# NIXIE_2.net
KiCad netlist of a schematic drawn in Altium Designer
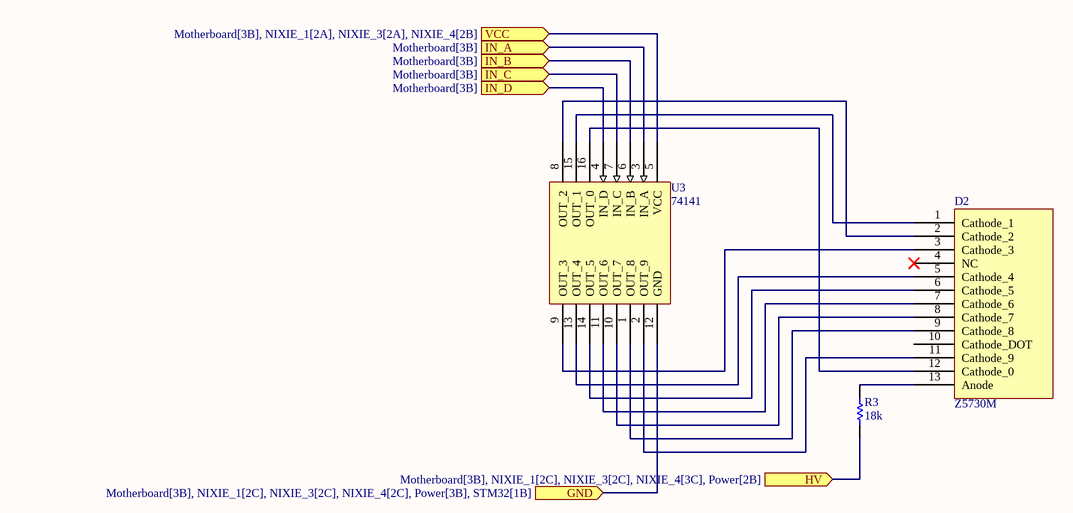
[diagram p0: NIXIE_2.SchDoc]

(export (version "E")
  (design (tool "Eeschema 10.0.6"))
  (components
    (comp (ref "D2") (value "Z5730M") (footprint "Z5730M") (libsource (lib "Z5730M") (part "Z5730M")))
    (comp (ref "R3")
      (value "18k")
      (footprint "RESC2013X60X40LL20T25")
      (fields (field (name "MANUFACTURER") "Panasonic") (field (name "PART NUMBER") "ERA6AEB183V"))
      (libsource (lib "Altium Content Vault") (part "RES"))
    )
    (comp (ref "U3") (value "74141") (footprint "DIP-16") (libsource (lib "Z5730M") (part "74141")))
  )
  (nets
    (net (code "1") (name "/GND") (class "Default")
      (node (ref "U3") (pin "12") (pinfunction "GND_12") (pintype "power_in"))
    )
    (net (code "2") (name "/HV") (class "Default")
      (node (ref "R3") (pin "1") (pinfunction "1_1") (pintype "passive"))
    )
    (net (code "3") (name "/IN_A") (class "Default")
      (node (ref "U3") (pin "3") (pinfunction "IN_A_3") (pintype "input"))
    )
    (net (code "4") (name "/IN_B") (class "Default")
      (node (ref "U3") (pin "6") (pinfunction "IN_B_6") (pintype "input"))
    )
    (net (code "5") (name "/IN_C") (class "Default")
      (node (ref "U3") (pin "7") (pinfunction "IN_C_7") (pintype "input"))
    )
    (net (code "6") (name "/IN_D") (class "Default")
      (node (ref "U3") (pin "4") (pinfunction "IN_D_4") (pintype "input"))
    )
    (net (code "7") (name "/VCC") (class "Default")
      (node (ref "U3") (pin "5") (pinfunction "VCC_5") (pintype "power_in"))
    )
    (net (code "8") (name "Net-(D2-Anode)") (class "Default")
      (node (ref "D2") (pin "13") (pinfunction "Anode_13") (pintype "passive"))
      (node (ref "R3") (pin "2") (pinfunction "2_2") (pintype "passive"))
    )
    (net (code "9") (name "Net-(D2-Cathode_0)") (class "Default")
      (node (ref "D2") (pin "12") (pinfunction "Cathode_0_12") (pintype "passive"))
      (node (ref "U3") (pin "16") (pinfunction "OUT_0_16") (pintype "open_collector"))
    )
    (net (code "10") (name "Net-(D2-Cathode_1)") (class "Default")
      (node (ref "D2") (pin "1") (pinfunction "Cathode_1_1") (pintype "passive"))
      (node (ref "U3") (pin "15") (pinfunction "OUT_1_15") (pintype "open_collector"))
    )
    (net (code "11") (name "Net-(D2-Cathode_2)") (class "Default")
      (node (ref "D2") (pin "2") (pinfunction "Cathode_2_2") (pintype "passive"))
      (node (ref "U3") (pin "8") (pinfunction "OUT_2_8") (pintype "open_collector"))
    )
    (net (code "12") (name "Net-(D2-Cathode_3)") (class "Default")
      (node (ref "D2") (pin "3") (pinfunction "Cathode_3_3") (pintype "passive"))
      (node (ref "U3") (pin "9") (pinfunction "OUT_3_9") (pintype "open_collector"))
    )
    (net (code "13") (name "Net-(D2-Cathode_4)") (class "Default")
      (node (ref "D2") (pin "5") (pinfunction "Cathode_4_5") (pintype "passive"))
      (node (ref "U3") (pin "13") (pinfunction "OUT_4_13") (pintype "open_collector"))
    )
    (net (code "14") (name "Net-(D2-Cathode_5)") (class "Default")
      (node (ref "D2") (pin "6") (pinfunction "Cathode_5_6") (pintype "passive"))
      (node (ref "U3") (pin "14") (pinfunction "OUT_5_14") (pintype "open_collector"))
    )
    (net (code "15") (name "Net-(D2-Cathode_6)") (class "Default")
      (node (ref "D2") (pin "7") (pinfunction "Cathode_6_7") (pintype "passive"))
      (node (ref "U3") (pin "11") (pinfunction "OUT_6_11") (pintype "open_collector"))
    )
    (net (code "16") (name "Net-(D2-Cathode_7)") (class "Default")
      (node (ref "D2") (pin "8") (pinfunction "Cathode_7_8") (pintype "passive"))
      (node (ref "U3") (pin "10") (pinfunction "OUT_7_10") (pintype "open_collector"))
    )
    (net (code "17") (name "Net-(D2-Cathode_8)") (class "Default")
      (node (ref "D2") (pin "9") (pinfunction "Cathode_8_9") (pintype "passive"))
      (node (ref "U3") (pin "1") (pinfunction "OUT_8_1") (pintype "open_collector"))
    )
    (net (code "18") (name "Net-(D2-Cathode_9)") (class "Default")
      (node (ref "D2") (pin "11") (pinfunction "Cathode_9_11") (pintype "passive"))
      (node (ref "U3") (pin "2") (pinfunction "OUT_9_2") (pintype "open_collector"))
    )
    (net (code "19") (name "unconnected-(D2-Cathode_DOT-Pad10)") (class "Default")
      (node (ref "D2") (pin "10") (pinfunction "Cathode_DOT_10") (pintype "passive"))
    )
    (net (code "20") (name "unconnected-(D2-NC-Pad4)") (class "Default")
      (node (ref "D2") (pin "4") (pinfunction "NC_4") (pintype "passive+no_connect"))
    )
  )
)
